# Phi.net
KiCad netlist of a schematic drawn in EAGLE
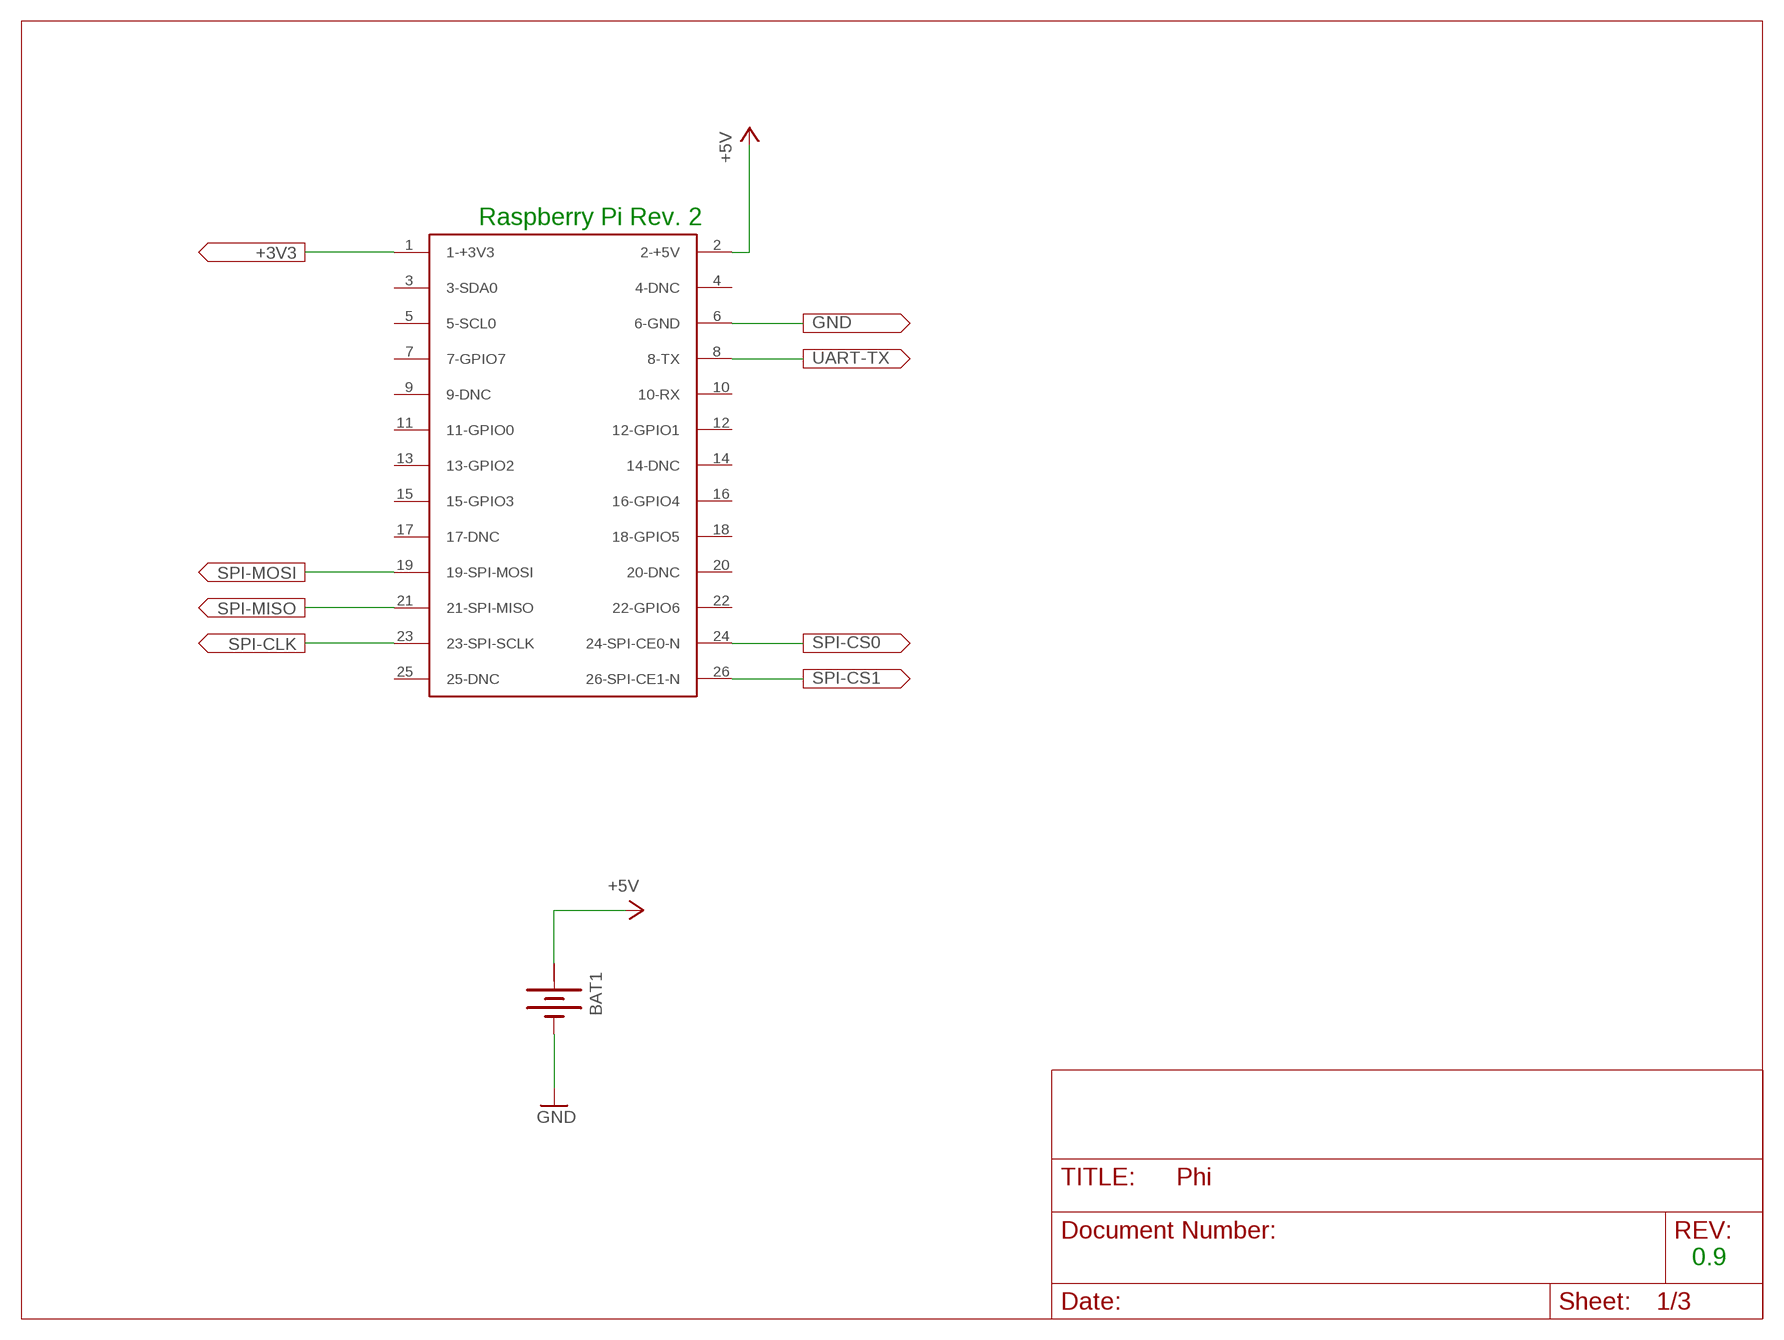
[diagram p0: schematic, sheet 1]
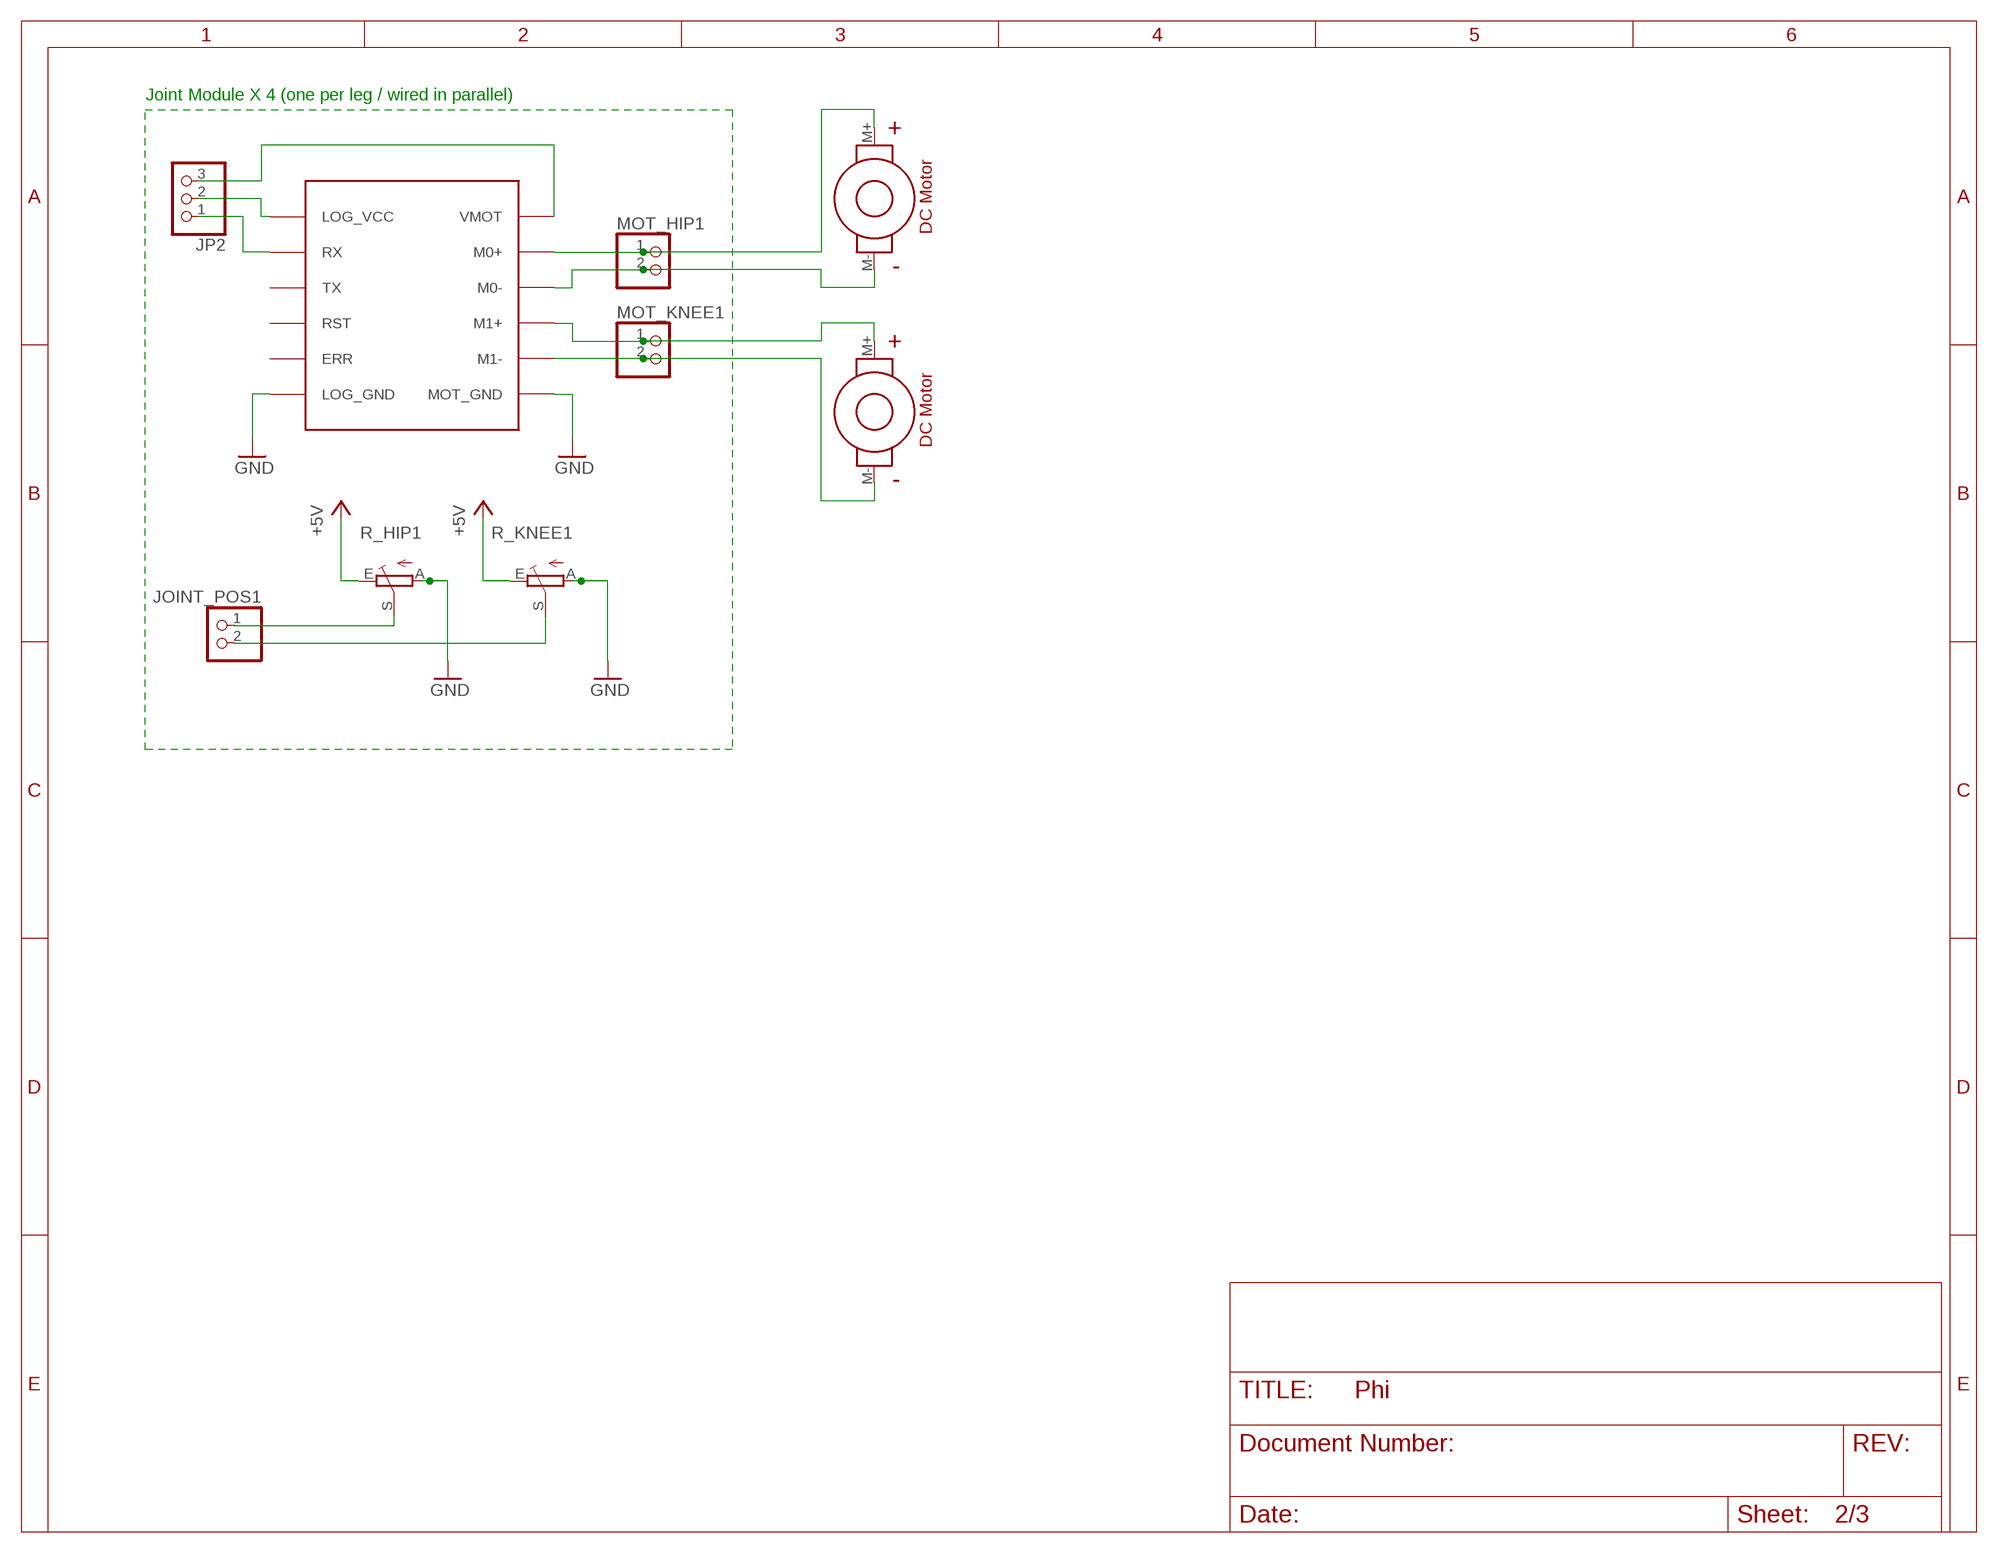
[diagram p1: schematic, sheet 2]
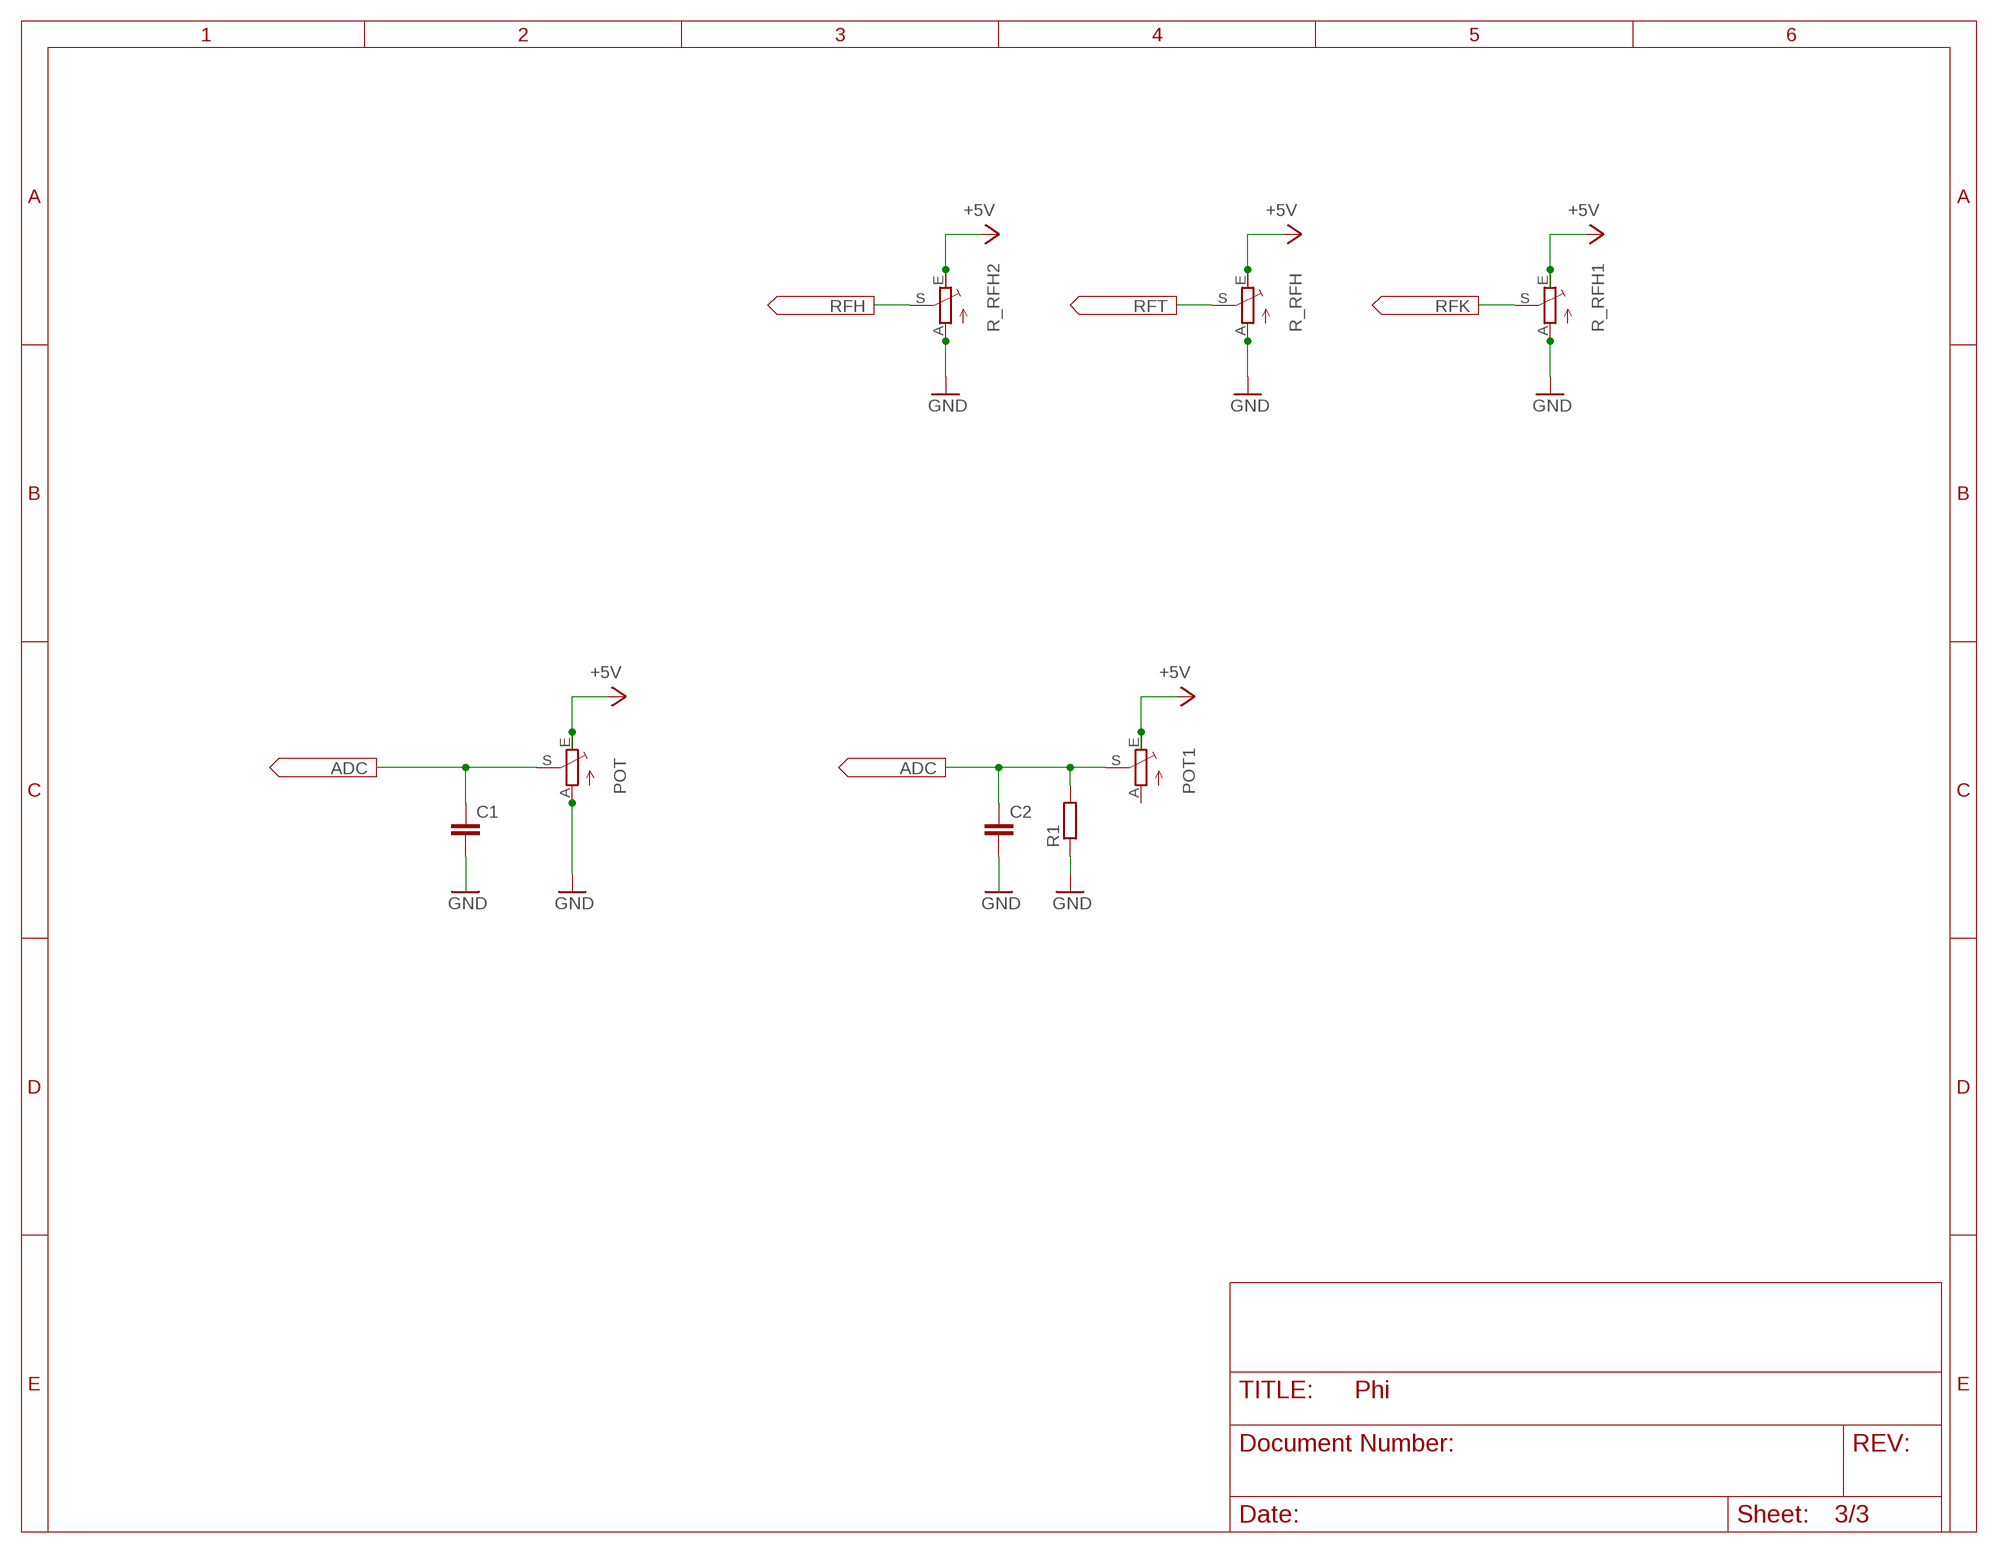
[diagram p2: schematic, sheet 3]

(export (version "E")
  (design (tool "Eeschema 10.0.6"))
  (components
    (comp (ref "BAT1")
      (value "BATTERY")
      (footprint "eagle-import:BATTERY")
      (libsource (lib "eagle-import") (part "BATTERY"))
    )
    (comp (ref "U$1")
      (value "RASPBERRY-PI")
      (footprint "eagle-import:RASPBERRY-PI")
      (libsource (lib "eagle-import") (part "RASPBERRY-PI"))
    )
    (comp (ref "JOINT_POS1")
      (value "PINHD-1X2")
      (footprint "eagle-import:1X02")
      (libsource (lib "eagle-import") (part "PINHD-1X2"))
    )
    (comp (ref "JP2")
      (value "PINHD-1X3")
      (footprint "eagle-import:1X03")
      (libsource (lib "eagle-import") (part "PINHD-1X3"))
    )
    (comp (ref "MOT_HIP1")
      (value "PINHD-1X2")
      (footprint "eagle-import:1X02")
      (libsource (lib "eagle-import") (part "PINHD-1X2"))
    )
    (comp (ref "MOT_KNEE1")
      (value "PINHD-1X2")
      (footprint "eagle-import:1X02")
      (libsource (lib "eagle-import") (part "PINHD-1X2"))
    )
    (comp (ref "R_HIP1")
      (value "TRIM_EU-B25P")
      (footprint "eagle-import:B25P")
      (libsource (lib "eagle-import") (part "TRIM_EU-B25P"))
    )
    (comp (ref "R_KNEE1")
      (value "TRIM_EU-B25P")
      (footprint "eagle-import:B25P")
      (libsource (lib "eagle-import") (part "TRIM_EU-B25P"))
    )
    (comp (ref "U$5")
      (value "QIK_2S9V1")
      (footprint "eagle-import:QIK_2S9V1_BOARD")
      (libsource (lib "eagle-import") (part "QIK_2S9V1"))
    )
    (comp (ref "U$6")
      (value "DC-MOTOR")
      (footprint "eagle-import:DC-MOTOR")
      (libsource (lib "eagle-import") (part "DC-MOTOR"))
    )
    (comp (ref "U$7")
      (value "DC-MOTOR")
      (footprint "eagle-import:DC-MOTOR")
      (libsource (lib "eagle-import") (part "DC-MOTOR"))
    )
    (comp (ref "C1")
      (value "C2,5-3")
      (footprint "eagle-import:C2.5-3")
      (libsource (lib "eagle-import") (part "C2,5-3"))
    )
    (comp (ref "C2")
      (value "C2,5-3")
      (footprint "eagle-import:C2.5-3")
      (libsource (lib "eagle-import") (part "C2,5-3"))
    )
    (comp (ref "POT")
      (value "TRIM_EU-B25P")
      (footprint "eagle-import:B25P")
      (libsource (lib "eagle-import") (part "TRIM_EU-B25P"))
    )
    (comp (ref "POT1")
      (value "TRIM_EU-B25P")
      (footprint "eagle-import:B25P")
      (libsource (lib "eagle-import") (part "TRIM_EU-B25P"))
    )
    (comp (ref "R1")
      (value "R-EU_0204/2V")
      (footprint "eagle-import:0204V")
      (libsource (lib "eagle-import") (part "R-EU_0204/2V"))
    )
    (comp (ref "R_RFH")
      (value "TRIM_EU-B25P")
      (footprint "eagle-import:B25P")
      (libsource (lib "eagle-import") (part "TRIM_EU-B25P"))
    )
    (comp (ref "R_RFH1")
      (value "TRIM_EU-B25P")
      (footprint "eagle-import:B25P")
      (libsource (lib "eagle-import") (part "TRIM_EU-B25P"))
    )
    (comp (ref "R_RFH2")
      (value "TRIM_EU-B25P")
      (footprint "eagle-import:B25P")
      (libsource (lib "eagle-import") (part "TRIM_EU-B25P"))
    )
  )
  (nets
    (net (code "1") (name "+") (class "Default")
      (node (ref "BAT1") (pin "+@1") (pinfunction "+_+@1") (pintype "power_in"))
    )
    (net (code "2") (name "+5V") (class "Default")
      (node (ref "BAT1") (pin "+") (pinfunction "+_+") (pintype "power_in"))
      (node (ref "JP2") (pin "3") (pinfunction "3_3") (pintype "passive"))
      (node (ref "POT") (pin "E") (pinfunction "E_E") (pintype "passive"))
      (node (ref "POT1") (pin "E") (pinfunction "E_E") (pintype "passive"))
      (node (ref "R_HIP1") (pin "E") (pinfunction "E_E") (pintype "passive"))
      (node (ref "R_KNEE1") (pin "E") (pinfunction "E_E") (pintype "passive"))
      (node (ref "R_RFH") (pin "E") (pinfunction "E_E") (pintype "passive"))
      (node (ref "R_RFH1") (pin "E") (pinfunction "E_E") (pintype "passive"))
      (node (ref "R_RFH2") (pin "E") (pinfunction "E_E") (pintype "passive"))
      (node (ref "U$1") (pin "2") (pinfunction "2-+5V_2") (pintype "bidirectional"))
      (node (ref "U$5") (pin "VMOT") (pinfunction "VMOT_VMOT") (pintype "bidirectional"))
    )
    (net (code "3") (name "GND") (class "Default")
      (node (ref "BAT1") (pin "-") (pinfunction "-_-") (pintype "power_in"))
      (node (ref "POT") (pin "A") (pinfunction "A_A") (pintype "passive"))
      (node (ref "R1") (pin "1") (pinfunction "1_1") (pintype "passive"))
      (node (ref "R_HIP1") (pin "A") (pinfunction "A_A") (pintype "passive"))
      (node (ref "R_KNEE1") (pin "A") (pinfunction "A_A") (pintype "passive"))
      (node (ref "R_RFH") (pin "A") (pinfunction "A_A") (pintype "passive"))
      (node (ref "R_RFH1") (pin "A") (pinfunction "A_A") (pintype "passive"))
      (node (ref "R_RFH2") (pin "A") (pinfunction "A_A") (pintype "passive"))
      (node (ref "U$5") (pin "GND") (pinfunction "LOG_GND_GND") (pintype "bidirectional"))
      (node (ref "U$5") (pin "GND2") (pinfunction "MOT_GND_GND2") (pintype "bidirectional"))
    )
    (net (code "4") (name "Net-(C1-Pad1)") (class "Default")
      (node (ref "C1") (pin "1") (pinfunction "1_1") (pintype "passive"))
      (node (ref "POT") (pin "S") (pinfunction "S_S") (pintype "passive"))
    )
    (net (code "5") (name "Net-(C2-Pad1)") (class "Default")
      (node (ref "C2") (pin "1") (pinfunction "1_1") (pintype "passive"))
      (node (ref "POT1") (pin "S") (pinfunction "S_S") (pintype "passive"))
      (node (ref "R1") (pin "2") (pinfunction "2_2") (pintype "passive"))
    )
    (net (code "6") (name "Net-(JOINT_POS1-Pad1)") (class "Default")
      (node (ref "JOINT_POS1") (pin "1") (pinfunction "1_1") (pintype "passive"))
      (node (ref "R_HIP1") (pin "S") (pinfunction "S_S") (pintype "passive"))
    )
    (net (code "7") (name "Net-(JOINT_POS1-Pad2)") (class "Default")
      (node (ref "JOINT_POS1") (pin "2") (pinfunction "2_2") (pintype "passive"))
      (node (ref "R_KNEE1") (pin "S") (pinfunction "S_S") (pintype "passive"))
    )
    (net (code "8") (name "Net-(JP2-Pad1)") (class "Default")
      (node (ref "JP2") (pin "1") (pinfunction "1_1") (pintype "passive"))
      (node (ref "U$5") (pin "RX") (pinfunction "RX_RX") (pintype "bidirectional"))
    )
    (net (code "9") (name "Net-(MOT_HIP1-Pad1)") (class "Default")
      (node (ref "MOT_HIP1") (pin "1") (pinfunction "1_1") (pintype "passive"))
      (node (ref "U$5") (pin "M0+") (pinfunction "M0+_M0+") (pintype "bidirectional"))
      (node (ref "U$6") (pin "M+") (pinfunction "M+_M+") (pintype "bidirectional"))
    )
    (net (code "10") (name "Net-(MOT_HIP1-Pad2)") (class "Default")
      (node (ref "MOT_HIP1") (pin "2") (pinfunction "2_2") (pintype "passive"))
      (node (ref "U$5") (pin "M0-") (pinfunction "M0-_M0-") (pintype "bidirectional"))
      (node (ref "U$6") (pin "M-") (pinfunction "M-_M-") (pintype "bidirectional"))
    )
    (net (code "11") (name "Net-(MOT_KNEE1-Pad1)") (class "Default")
      (node (ref "MOT_KNEE1") (pin "1") (pinfunction "1_1") (pintype "passive"))
      (node (ref "U$5") (pin "M1+") (pinfunction "M1+_M1+") (pintype "bidirectional"))
      (node (ref "U$7") (pin "M+") (pinfunction "M+_M+") (pintype "bidirectional"))
    )
    (net (code "12") (name "Net-(MOT_KNEE1-Pad2)") (class "Default")
      (node (ref "MOT_KNEE1") (pin "2") (pinfunction "2_2") (pintype "passive"))
      (node (ref "U$5") (pin "M1-") (pinfunction "M1-_M1-") (pintype "bidirectional"))
      (node (ref "U$7") (pin "M-") (pinfunction "M-_M-") (pintype "bidirectional"))
    )
    (net (code "13") (name "Net-(U$5-LOG_VCC)") (class "Default")
      (node (ref "JP2") (pin "2") (pinfunction "2_2") (pintype "passive"))
      (node (ref "U$5") (pin "VCC") (pinfunction "LOG_VCC_VCC") (pintype "bidirectional"))
    )
    (net (code "14") (name "unconnected-(C1-Pad2)") (class "Default")
      (node (ref "C1") (pin "2") (pinfunction "2_2") (pintype "passive"))
    )
    (net (code "15") (name "unconnected-(C2-Pad2)") (class "Default")
      (node (ref "C2") (pin "2") (pinfunction "2_2") (pintype "passive"))
    )
    (net (code "16") (name "unconnected-(POT1-PadA)") (class "Default")
      (node (ref "POT1") (pin "A") (pinfunction "A_A") (pintype "passive"))
    )
    (net (code "17") (name "unconnected-(R_RFH-PadS)") (class "Default")
      (node (ref "R_RFH") (pin "S") (pinfunction "S_S") (pintype "passive"))
    )
    (net (code "18") (name "unconnected-(R_RFH1-PadS)") (class "Default")
      (node (ref "R_RFH1") (pin "S") (pinfunction "S_S") (pintype "passive"))
    )
    (net (code "19") (name "unconnected-(R_RFH2-PadS)") (class "Default")
      (node (ref "R_RFH2") (pin "S") (pinfunction "S_S") (pintype "passive"))
    )
    (net (code "20") (name "unconnected-(U$1-1-+3V3-Pad1)") (class "Default")
      (node (ref "U$1") (pin "1") (pinfunction "1-+3V3_1") (pintype "bidirectional"))
    )
    (net (code "21") (name "unconnected-(U$1-3-SDA0-Pad3)") (class "Default")
      (node (ref "U$1") (pin "3") (pinfunction "3-SDA0_3") (pintype "bidirectional"))
    )
    (net (code "22") (name "unconnected-(U$1-4-DNC-Pad4)") (class "Default")
      (node (ref "U$1") (pin "4") (pinfunction "4-DNC_4") (pintype "bidirectional"))
    )
    (net (code "23") (name "unconnected-(U$1-5-SCL0-Pad5)") (class "Default")
      (node (ref "U$1") (pin "5") (pinfunction "5-SCL0_5") (pintype "bidirectional"))
    )
    (net (code "24") (name "unconnected-(U$1-6-GND-Pad6)") (class "Default")
      (node (ref "U$1") (pin "6") (pinfunction "6-GND_6") (pintype "bidirectional"))
    )
    (net (code "25") (name "unconnected-(U$1-7-GPIO7-Pad7)") (class "Default")
      (node (ref "U$1") (pin "7") (pinfunction "7-GPIO7_7") (pintype "bidirectional"))
    )
    (net (code "26") (name "unconnected-(U$1-8-TX-Pad8)") (class "Default")
      (node (ref "U$1") (pin "8") (pinfunction "8-TX_8") (pintype "bidirectional"))
    )
    (net (code "27") (name "unconnected-(U$1-9-DNC-Pad9)") (class "Default")
      (node (ref "U$1") (pin "9") (pinfunction "9-DNC_9") (pintype "bidirectional"))
    )
    (net (code "28") (name "unconnected-(U$1-10-RX-Pad10)") (class "Default")
      (node (ref "U$1") (pin "10") (pinfunction "10-RX_10") (pintype "bidirectional"))
    )
    (net (code "29") (name "unconnected-(U$1-11-GPIO0-Pad11)") (class "Default")
      (node (ref "U$1") (pin "11") (pinfunction "11-GPIO0_11") (pintype "bidirectional"))
    )
    (net (code "30") (name "unconnected-(U$1-12-GPIO1-Pad12)") (class "Default")
      (node (ref "U$1") (pin "12") (pinfunction "12-GPIO1_12") (pintype "bidirectional"))
    )
    (net (code "31") (name "unconnected-(U$1-13-GPIO2-Pad13)") (class "Default")
      (node (ref "U$1") (pin "13") (pinfunction "13-GPIO2_13") (pintype "bidirectional"))
    )
    (net (code "32") (name "unconnected-(U$1-14-DNC-Pad14)") (class "Default")
      (node (ref "U$1") (pin "14") (pinfunction "14-DNC_14") (pintype "bidirectional"))
    )
    (net (code "33") (name "unconnected-(U$1-15-GPIO3-Pad15)") (class "Default")
      (node (ref "U$1") (pin "15") (pinfunction "15-GPIO3_15") (pintype "bidirectional"))
    )
    (net (code "34") (name "unconnected-(U$1-16-GPIO4-Pad16)") (class "Default")
      (node (ref "U$1") (pin "16") (pinfunction "16-GPIO4_16") (pintype "bidirectional"))
    )
    (net (code "35") (name "unconnected-(U$1-17-DNC-Pad17)") (class "Default")
      (node (ref "U$1") (pin "17") (pinfunction "17-DNC_17") (pintype "bidirectional"))
    )
    (net (code "36") (name "unconnected-(U$1-18-GPIO5-Pad18)") (class "Default")
      (node (ref "U$1") (pin "18") (pinfunction "18-GPIO5_18") (pintype "bidirectional"))
    )
    (net (code "37") (name "unconnected-(U$1-19-SPI-MOSI-Pad19)") (class "Default")
      (node (ref "U$1") (pin "19") (pinfunction "19-SPI-MOSI_19") (pintype "bidirectional"))
    )
    (net (code "38") (name "unconnected-(U$1-20-DNC-Pad20)") (class "Default")
      (node (ref "U$1") (pin "20") (pinfunction "20-DNC_20") (pintype "bidirectional"))
    )
    (net (code "39") (name "unconnected-(U$1-21-SPI-MISO-Pad21)") (class "Default")
      (node (ref "U$1") (pin "21") (pinfunction "21-SPI-MISO_21") (pintype "bidirectional"))
    )
    (net (code "40") (name "unconnected-(U$1-22-GPIO6-Pad22)") (class "Default")
      (node (ref "U$1") (pin "22") (pinfunction "22-GPIO6_22") (pintype "bidirectional"))
    )
    (net (code "41") (name "unconnected-(U$1-23-SPI-SCLK-Pad23)") (class "Default")
      (node (ref "U$1") (pin "23") (pinfunction "23-SPI-SCLK_23") (pintype "bidirectional"))
    )
    (net (code "42") (name "unconnected-(U$1-24-SPI-CE0-N-Pad24)") (class "Default")
      (node (ref "U$1") (pin "24") (pinfunction "24-SPI-CE0-N_24") (pintype "bidirectional"))
    )
    (net (code "43") (name "unconnected-(U$1-25-DNC-Pad25)") (class "Default")
      (node (ref "U$1") (pin "25") (pinfunction "25-DNC_25") (pintype "bidirectional"))
    )
    (net (code "44") (name "unconnected-(U$1-26-SPI-CE1-N-Pad26)") (class "Default")
      (node (ref "U$1") (pin "26") (pinfunction "26-SPI-CE1-N_26") (pintype "bidirectional"))
    )
    (net (code "45") (name "unconnected-(U$5-PadERR)") (class "Default")
      (node (ref "U$5") (pin "ERR") (pinfunction "ERR_ERR") (pintype "bidirectional"))
    )
    (net (code "46") (name "unconnected-(U$5-PadRST)") (class "Default")
      (node (ref "U$5") (pin "RST") (pinfunction "RST_RST") (pintype "bidirectional"))
    )
    (net (code "47") (name "unconnected-(U$5-PadTX)") (class "Default")
      (node (ref "U$5") (pin "TX") (pinfunction "TX_TX") (pintype "bidirectional"))
    )
  )
)
